# 5_-5_9_-9.net
KiCad netlist of a schematic drawn in EAGLE
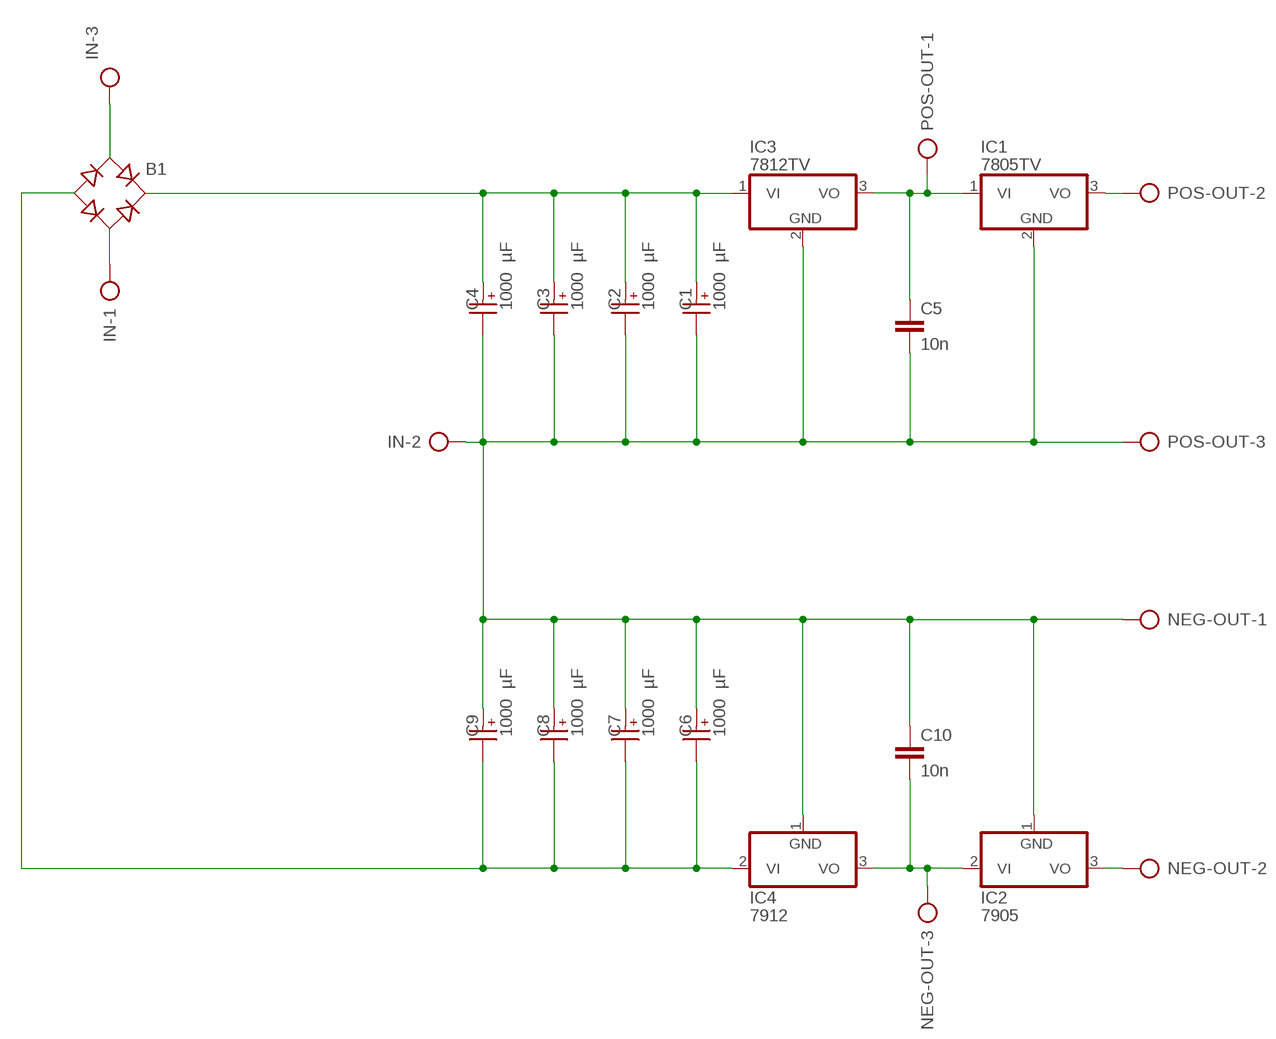
[diagram p0: schematic, sheet 1]

(export (version "E")
  (design (tool "Eeschema 10.0.6"))
  (components
    (comp (ref "B1")
      (value "RB1A")
      (footprint "eagle-import:RB1A")
      (libsource (lib "eagle-import") (part "RB1A"))
    )
    (comp (ref "C1")
      (value "1000 µF")
      (footprint "eagle-import:WCAP-ATG8_10X12.5(DXL)")
      (libsource (lib "eagle-import") (part "WCAP-ATG8_10X12.5_860010275016"))
    )
    (comp (ref "C2")
      (value "1000 µF")
      (footprint "eagle-import:WCAP-ATG8_10X12.5(DXL)")
      (libsource (lib "eagle-import") (part "WCAP-ATG8_10X12.5_860010275016"))
    )
    (comp (ref "C3")
      (value "1000 µF")
      (footprint "eagle-import:WCAP-ATG8_10X12.5(DXL)")
      (libsource (lib "eagle-import") (part "WCAP-ATG8_10X12.5_860010275016"))
    )
    (comp (ref "C4")
      (value "1000 µF")
      (footprint "eagle-import:WCAP-ATG8_10X12.5(DXL)")
      (libsource (lib "eagle-import") (part "WCAP-ATG8_10X12.5_860010275016"))
    )
    (comp (ref "C5")
      (value "10n")
      (footprint "eagle-import:C025-025X050")
      (libsource (lib "eagle-import") (part "C-EU025-025X050"))
    )
    (comp (ref "C6")
      (value "1000 µF")
      (footprint "eagle-import:WCAP-ATG8_10X12.5(DXL)")
      (libsource (lib "eagle-import") (part "WCAP-ATG8_10X12.5_860010275016"))
    )
    (comp (ref "C7")
      (value "1000 µF")
      (footprint "eagle-import:WCAP-ATG8_10X12.5(DXL)")
      (libsource (lib "eagle-import") (part "WCAP-ATG8_10X12.5_860010275016"))
    )
    (comp (ref "C8")
      (value "1000 µF")
      (footprint "eagle-import:WCAP-ATG8_10X12.5(DXL)")
      (libsource (lib "eagle-import") (part "WCAP-ATG8_10X12.5_860010275016"))
    )
    (comp (ref "C9")
      (value "1000 µF")
      (footprint "eagle-import:WCAP-ATG8_10X12.5(DXL)")
      (libsource (lib "eagle-import") (part "WCAP-ATG8_10X12.5_860010275016"))
    )
    (comp (ref "C10")
      (value "10n")
      (footprint "eagle-import:C025-025X050")
      (libsource (lib "eagle-import") (part "C-EU025-025X050"))
    )
    (comp (ref "IC1")
      (value "7805TV")
      (footprint "eagle-import:TO220V")
      (libsource (lib "eagle-import") (part "78TV05"))
    )
    (comp (ref "IC2")
      (value "7905")
      (footprint "eagle-import:TO220H")
      (libsource (lib "eagle-import") (part "79T05"))
    )
    (comp (ref "IC3")
      (value "7812TV")
      (footprint "eagle-import:TO220V")
      (libsource (lib "eagle-import") (part "78TV12"))
    )
    (comp (ref "IC4")
      (value "7912")
      (footprint "eagle-import:TO220H")
      (libsource (lib "eagle-import") (part "79T12"))
    )
    (comp (ref "IN")
      (value "AK300/3")
      (footprint "eagle-import:AK300_3")
      (libsource (lib "eagle-import") (part "AK300/3"))
    )
    (comp (ref "NEG-OUT")
      (value "AK300/3")
      (footprint "eagle-import:AK300_3")
      (libsource (lib "eagle-import") (part "AK300/3"))
    )
    (comp (ref "POS-OUT")
      (value "AK300/3")
      (footprint "eagle-import:AK300_3")
      (libsource (lib "eagle-import") (part "AK300/3"))
    )
  )
  (nets
    (net (code "1") (name "Net-(C1-+)") (class "Default")
      (node (ref "B1") (pin "+") (pinfunction "+_+") (pintype "passive"))
      (node (ref "C1") (pin "1") (pinfunction "+_1") (pintype "passive"))
      (node (ref "C2") (pin "1") (pinfunction "+_1") (pintype "passive"))
      (node (ref "C3") (pin "1") (pinfunction "+_1") (pintype "passive"))
      (node (ref "C4") (pin "1") (pinfunction "+_1") (pintype "passive"))
      (node (ref "IC3") (pin "1") (pinfunction "VI_1") (pintype "input"))
    )
    (net (code "2") (name "Net-(C1--)") (class "Default")
      (node (ref "C1") (pin "2") (pinfunction "-_2") (pintype "passive"))
      (node (ref "C10") (pin "1") (pinfunction "1_1") (pintype "passive"))
      (node (ref "C2") (pin "2") (pinfunction "-_2") (pintype "passive"))
      (node (ref "C3") (pin "2") (pinfunction "-_2") (pintype "passive"))
      (node (ref "C4") (pin "2") (pinfunction "-_2") (pintype "passive"))
      (node (ref "C5") (pin "2") (pinfunction "2_2") (pintype "passive"))
      (node (ref "C6") (pin "1") (pinfunction "+_1") (pintype "passive"))
      (node (ref "C7") (pin "1") (pinfunction "+_1") (pintype "passive"))
      (node (ref "C8") (pin "1") (pinfunction "+_1") (pintype "passive"))
      (node (ref "C9") (pin "1") (pinfunction "+_1") (pintype "passive"))
      (node (ref "IC1") (pin "2") (pinfunction "GND_2") (pintype "passive"))
      (node (ref "IC2") (pin "1") (pinfunction "GND_1") (pintype "passive"))
      (node (ref "IC3") (pin "2") (pinfunction "GND_2") (pintype "passive"))
      (node (ref "IC4") (pin "1") (pinfunction "GND_1") (pintype "passive"))
      (node (ref "IN") (pin "2") (pinfunction "KL_2") (pintype "passive"))
      (node (ref "NEG-OUT") (pin "1") (pinfunction "KL_1") (pintype "passive"))
      (node (ref "POS-OUT") (pin "3") (pinfunction "KL_3") (pintype "passive"))
    )
    (net (code "3") (name "Net-(C6--)") (class "Default")
      (node (ref "B1") (pin "-") (pinfunction "-_-") (pintype "passive"))
      (node (ref "C6") (pin "2") (pinfunction "-_2") (pintype "passive"))
      (node (ref "C7") (pin "2") (pinfunction "-_2") (pintype "passive"))
      (node (ref "C8") (pin "2") (pinfunction "-_2") (pintype "passive"))
      (node (ref "C9") (pin "2") (pinfunction "-_2") (pintype "passive"))
      (node (ref "IC4") (pin "2") (pinfunction "VI_2") (pintype "input"))
    )
    (net (code "4") (name "Net-(IC1-VI)") (class "Default")
      (node (ref "C5") (pin "1") (pinfunction "1_1") (pintype "passive"))
      (node (ref "IC1") (pin "1") (pinfunction "VI_1") (pintype "input"))
      (node (ref "IC3") (pin "3") (pinfunction "VO_3") (pintype "passive"))
      (node (ref "POS-OUT") (pin "1") (pinfunction "KL_1") (pintype "passive"))
    )
    (net (code "5") (name "Net-(IC1-VO)") (class "Default")
      (node (ref "IC1") (pin "3") (pinfunction "VO_3") (pintype "passive"))
      (node (ref "POS-OUT") (pin "2") (pinfunction "KL_2") (pintype "passive"))
    )
    (net (code "6") (name "Net-(IC2-VI)") (class "Default")
      (node (ref "C10") (pin "2") (pinfunction "2_2") (pintype "passive"))
      (node (ref "IC2") (pin "2") (pinfunction "VI_2") (pintype "input"))
      (node (ref "IC4") (pin "3") (pinfunction "VO_3") (pintype "passive"))
      (node (ref "NEG-OUT") (pin "3") (pinfunction "KL_3") (pintype "passive"))
    )
    (net (code "7") (name "Net-(IC2-VO)") (class "Default")
      (node (ref "IC2") (pin "3") (pinfunction "VO_3") (pintype "passive"))
      (node (ref "NEG-OUT") (pin "2") (pinfunction "KL_2") (pintype "passive"))
    )
    (net (code "8") (name "Net-(INA-KL)") (class "Default")
      (node (ref "B1") (pin "AC2") (pinfunction "AC2_AC2") (pintype "passive"))
      (node (ref "IN") (pin "1") (pinfunction "KL_1") (pintype "passive"))
    )
    (net (code "9") (name "Net-(INC-KL)") (class "Default")
      (node (ref "B1") (pin "AC1") (pinfunction "AC1_AC1") (pintype "passive"))
      (node (ref "IN") (pin "3") (pinfunction "KL_3") (pintype "passive"))
    )
  )
)
